# DAC8728_Output-buffers.net
KiCad netlist of a schematic drawn in Altium Designer
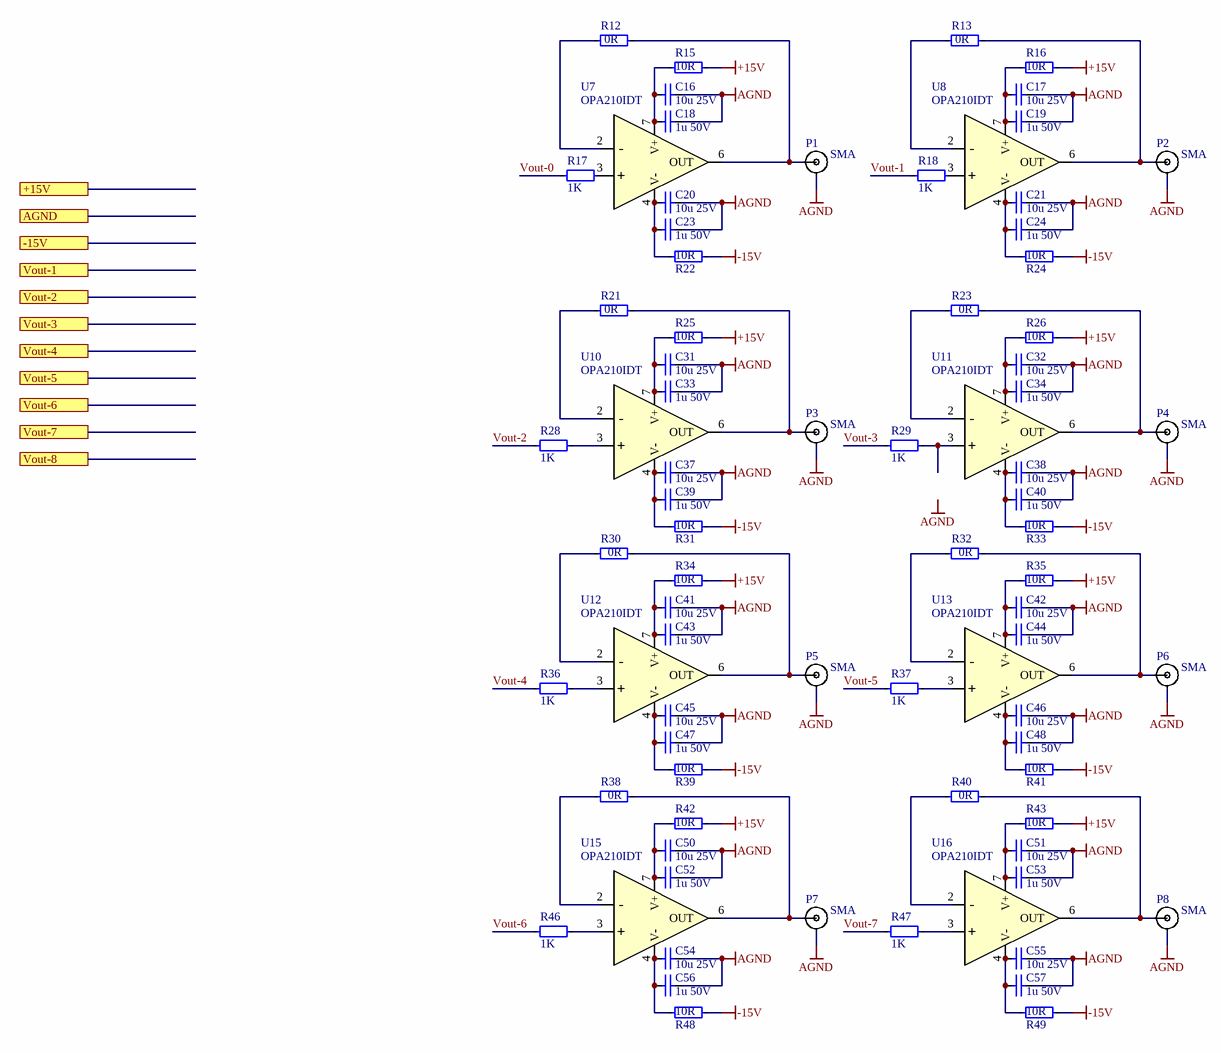
[diagram p0: DAC8728_Output-buffers.SchDoc]

(export (version "E")
  (design (tool "Eeschema 10.0.6"))
  (components
    (comp (ref "C16")
      (value "10u 25V")
      (footprint "cap0805MD")
      (fields
        (field (name "VOLTAGE") "25V")
        (field (name "AUTHOR") "EB")
        (field (name "CHECKED BY") "Unchecked")
      )
      (libsource (lib "TC_Parts") (part "capacitor"))
    )
    (comp (ref "C17")
      (value "10u 25V")
      (footprint "cap0805MD")
      (fields
        (field (name "VOLTAGE") "25V")
        (field (name "AUTHOR") "EB")
        (field (name "CHECKED BY") "Unchecked")
      )
      (libsource (lib "TC_Parts") (part "capacitor"))
    )
    (comp (ref "C18")
      (value "1u 50V")
      (footprint "cap0603MD")
      (fields
        (field (name "VOLTAGE") "50V")
        (field (name "AUTHOR") "Twe")
        (field (name "CHECKED BY") "Unchecked")
      )
      (libsource (lib "TC_Parts") (part "capacitor"))
    )
    (comp (ref "C19")
      (value "1u 50V")
      (footprint "cap0603MD")
      (fields
        (field (name "VOLTAGE") "50V")
        (field (name "AUTHOR") "Twe")
        (field (name "CHECKED BY") "Unchecked")
      )
      (libsource (lib "TC_Parts") (part "capacitor"))
    )
    (comp (ref "C20")
      (value "10u 25V")
      (footprint "cap0805MD")
      (fields
        (field (name "VOLTAGE") "25V")
        (field (name "AUTHOR") "EB")
        (field (name "CHECKED BY") "Unchecked")
      )
      (libsource (lib "TC_Parts") (part "capacitor"))
    )
    (comp (ref "C21")
      (value "10u 25V")
      (footprint "cap0805MD")
      (fields
        (field (name "VOLTAGE") "25V")
        (field (name "AUTHOR") "EB")
        (field (name "CHECKED BY") "Unchecked")
      )
      (libsource (lib "TC_Parts") (part "capacitor"))
    )
    (comp (ref "C23")
      (value "1u 50V")
      (footprint "cap0603MD")
      (fields
        (field (name "VOLTAGE") "50V")
        (field (name "AUTHOR") "Twe")
        (field (name "CHECKED BY") "Unchecked")
      )
      (libsource (lib "TC_Parts") (part "capacitor"))
    )
    (comp (ref "C24")
      (value "1u 50V")
      (footprint "cap0603MD")
      (fields
        (field (name "VOLTAGE") "50V")
        (field (name "AUTHOR") "Twe")
        (field (name "CHECKED BY") "Unchecked")
      )
      (libsource (lib "TC_Parts") (part "capacitor"))
    )
    (comp (ref "C31")
      (value "10u 25V")
      (footprint "cap0805MD")
      (fields
        (field (name "VOLTAGE") "25V")
        (field (name "AUTHOR") "EB")
        (field (name "CHECKED BY") "Unchecked")
      )
      (libsource (lib "TC_Parts") (part "capacitor"))
    )
    (comp (ref "C32")
      (value "10u 25V")
      (footprint "cap0805MD")
      (fields
        (field (name "VOLTAGE") "25V")
        (field (name "AUTHOR") "EB")
        (field (name "CHECKED BY") "Unchecked")
      )
      (libsource (lib "TC_Parts") (part "capacitor"))
    )
    (comp (ref "C33")
      (value "1u 50V")
      (footprint "cap0603MD")
      (fields
        (field (name "VOLTAGE") "50V")
        (field (name "AUTHOR") "Twe")
        (field (name "CHECKED BY") "Unchecked")
      )
      (libsource (lib "TC_Parts") (part "capacitor"))
    )
    (comp (ref "C34")
      (value "1u 50V")
      (footprint "cap0603MD")
      (fields
        (field (name "VOLTAGE") "50V")
        (field (name "AUTHOR") "Twe")
        (field (name "CHECKED BY") "Unchecked")
      )
      (libsource (lib "TC_Parts") (part "capacitor"))
    )
    (comp (ref "C37")
      (value "10u 25V")
      (footprint "cap0805MD")
      (fields
        (field (name "VOLTAGE") "25V")
        (field (name "AUTHOR") "EB")
        (field (name "CHECKED BY") "Unchecked")
      )
      (libsource (lib "TC_Parts") (part "capacitor"))
    )
    (comp (ref "C38")
      (value "10u 25V")
      (footprint "cap0805MD")
      (fields
        (field (name "VOLTAGE") "25V")
        (field (name "AUTHOR") "EB")
        (field (name "CHECKED BY") "Unchecked")
      )
      (libsource (lib "TC_Parts") (part "capacitor"))
    )
    (comp (ref "C39")
      (value "1u 50V")
      (footprint "cap0603MD")
      (fields
        (field (name "VOLTAGE") "50V")
        (field (name "AUTHOR") "Twe")
        (field (name "CHECKED BY") "Unchecked")
      )
      (libsource (lib "TC_Parts") (part "capacitor"))
    )
    (comp (ref "C40")
      (value "1u 50V")
      (footprint "cap0603MD")
      (fields
        (field (name "VOLTAGE") "50V")
        (field (name "AUTHOR") "Twe")
        (field (name "CHECKED BY") "Unchecked")
      )
      (libsource (lib "TC_Parts") (part "capacitor"))
    )
    (comp (ref "C41")
      (value "10u 25V")
      (footprint "cap0805MD")
      (fields
        (field (name "VOLTAGE") "25V")
        (field (name "AUTHOR") "EB")
        (field (name "CHECKED BY") "Unchecked")
      )
      (libsource (lib "TC_Parts") (part "capacitor"))
    )
    (comp (ref "C42")
      (value "10u 25V")
      (footprint "cap0805MD")
      (fields
        (field (name "VOLTAGE") "25V")
        (field (name "AUTHOR") "EB")
        (field (name "CHECKED BY") "Unchecked")
      )
      (libsource (lib "TC_Parts") (part "capacitor"))
    )
    (comp (ref "C43")
      (value "1u 50V")
      (footprint "cap0603MD")
      (fields
        (field (name "VOLTAGE") "50V")
        (field (name "AUTHOR") "Twe")
        (field (name "CHECKED BY") "Unchecked")
      )
      (libsource (lib "TC_Parts") (part "capacitor"))
    )
    (comp (ref "C44")
      (value "1u 50V")
      (footprint "cap0603MD")
      (fields
        (field (name "VOLTAGE") "50V")
        (field (name "AUTHOR") "Twe")
        (field (name "CHECKED BY") "Unchecked")
      )
      (libsource (lib "TC_Parts") (part "capacitor"))
    )
    (comp (ref "C45")
      (value "10u 25V")
      (footprint "cap0805MD")
      (fields
        (field (name "VOLTAGE") "25V")
        (field (name "AUTHOR") "EB")
        (field (name "CHECKED BY") "Unchecked")
      )
      (libsource (lib "TC_Parts") (part "capacitor"))
    )
    (comp (ref "C46")
      (value "10u 25V")
      (footprint "cap0805MD")
      (fields
        (field (name "VOLTAGE") "25V")
        (field (name "AUTHOR") "EB")
        (field (name "CHECKED BY") "Unchecked")
      )
      (libsource (lib "TC_Parts") (part "capacitor"))
    )
    (comp (ref "C47")
      (value "1u 50V")
      (footprint "cap0603MD")
      (fields
        (field (name "VOLTAGE") "50V")
        (field (name "AUTHOR") "Twe")
        (field (name "CHECKED BY") "Unchecked")
      )
      (libsource (lib "TC_Parts") (part "capacitor"))
    )
    (comp (ref "C48")
      (value "1u 50V")
      (footprint "cap0603MD")
      (fields
        (field (name "VOLTAGE") "50V")
        (field (name "AUTHOR") "Twe")
        (field (name "CHECKED BY") "Unchecked")
      )
      (libsource (lib "TC_Parts") (part "capacitor"))
    )
    (comp (ref "C50")
      (value "10u 25V")
      (footprint "cap0805MD")
      (fields
        (field (name "VOLTAGE") "25V")
        (field (name "AUTHOR") "EB")
        (field (name "CHECKED BY") "Unchecked")
      )
      (libsource (lib "TC_Parts") (part "capacitor"))
    )
    (comp (ref "C51")
      (value "10u 25V")
      (footprint "cap0805MD")
      (fields
        (field (name "VOLTAGE") "25V")
        (field (name "AUTHOR") "EB")
        (field (name "CHECKED BY") "Unchecked")
      )
      (libsource (lib "TC_Parts") (part "capacitor"))
    )
    (comp (ref "C52")
      (value "1u 50V")
      (footprint "cap0603MD")
      (fields
        (field (name "VOLTAGE") "50V")
        (field (name "AUTHOR") "Twe")
        (field (name "CHECKED BY") "Unchecked")
      )
      (libsource (lib "TC_Parts") (part "capacitor"))
    )
    (comp (ref "C53")
      (value "1u 50V")
      (footprint "cap0603MD")
      (fields
        (field (name "VOLTAGE") "50V")
        (field (name "AUTHOR") "Twe")
        (field (name "CHECKED BY") "Unchecked")
      )
      (libsource (lib "TC_Parts") (part "capacitor"))
    )
    (comp (ref "C54")
      (value "10u 25V")
      (footprint "cap0805MD")
      (fields
        (field (name "VOLTAGE") "25V")
        (field (name "AUTHOR") "EB")
        (field (name "CHECKED BY") "Unchecked")
      )
      (libsource (lib "TC_Parts") (part "capacitor"))
    )
    (comp (ref "C55")
      (value "10u 25V")
      (footprint "cap0805MD")
      (fields
        (field (name "VOLTAGE") "25V")
        (field (name "AUTHOR") "EB")
        (field (name "CHECKED BY") "Unchecked")
      )
      (libsource (lib "TC_Parts") (part "capacitor"))
    )
    (comp (ref "C56")
      (value "1u 50V")
      (footprint "cap0603MD")
      (fields
        (field (name "VOLTAGE") "50V")
        (field (name "AUTHOR") "Twe")
        (field (name "CHECKED BY") "Unchecked")
      )
      (libsource (lib "TC_Parts") (part "capacitor"))
    )
    (comp (ref "C57")
      (value "1u 50V")
      (footprint "cap0603MD")
      (fields
        (field (name "VOLTAGE") "50V")
        (field (name "AUTHOR") "Twe")
        (field (name "CHECKED BY") "Unchecked")
      )
      (libsource (lib "TC_Parts") (part "capacitor"))
    )
    (comp (ref "P1")
      (value "SMA")
      (footprint "619540-1")
      (description "SMA right angle through hole, 19mm, 50 Ohm")
      (fields
        (field (name "MANUFACTURER") "TE connectivity")
        (field (name "AUTHOR") "EB")
        (field (name "CHECKED BY") "Unchecked")
      )
      (libsource (lib "TC_Parts") (part "SMA"))
    )
    (comp (ref "P2")
      (value "SMA")
      (footprint "619540-1")
      (description "SMA right angle through hole, 19mm, 50 Ohm")
      (fields
        (field (name "MANUFACTURER") "TE connectivity")
        (field (name "AUTHOR") "EB")
        (field (name "CHECKED BY") "Unchecked")
      )
      (libsource (lib "TC_Parts") (part "SMA"))
    )
    (comp (ref "P3")
      (value "SMA")
      (footprint "619540-1")
      (description "SMA right angle through hole, 19mm, 50 Ohm")
      (fields
        (field (name "MANUFACTURER") "TE connectivity")
        (field (name "AUTHOR") "EB")
        (field (name "CHECKED BY") "Unchecked")
      )
      (libsource (lib "TC_Parts") (part "SMA"))
    )
    (comp (ref "P4")
      (value "SMA")
      (footprint "619540-1")
      (description "SMA right angle through hole, 19mm, 50 Ohm")
      (fields
        (field (name "MANUFACTURER") "TE connectivity")
        (field (name "AUTHOR") "EB")
        (field (name "CHECKED BY") "Unchecked")
      )
      (libsource (lib "TC_Parts") (part "SMA"))
    )
    (comp (ref "P5")
      (value "SMA")
      (footprint "619540-1")
      (description "SMA right angle through hole, 19mm, 50 Ohm")
      (fields
        (field (name "MANUFACTURER") "TE connectivity")
        (field (name "AUTHOR") "EB")
        (field (name "CHECKED BY") "Unchecked")
      )
      (libsource (lib "TC_Parts") (part "SMA"))
    )
    (comp (ref "P6")
      (value "SMA")
      (footprint "619540-1")
      (description "SMA right angle through hole, 19mm, 50 Ohm")
      (fields
        (field (name "MANUFACTURER") "TE connectivity")
        (field (name "AUTHOR") "EB")
        (field (name "CHECKED BY") "Unchecked")
      )
      (libsource (lib "TC_Parts") (part "SMA"))
    )
    (comp (ref "P7")
      (value "SMA")
      (footprint "619540-1")
      (description "SMA right angle through hole, 19mm, 50 Ohm")
      (fields
        (field (name "MANUFACTURER") "TE connectivity")
        (field (name "AUTHOR") "EB")
        (field (name "CHECKED BY") "Unchecked")
      )
      (libsource (lib "TC_Parts") (part "SMA"))
    )
    (comp (ref "P8")
      (value "SMA")
      (footprint "619540-1")
      (description "SMA right angle through hole, 19mm, 50 Ohm")
      (fields
        (field (name "MANUFACTURER") "TE connectivity")
        (field (name "AUTHOR") "EB")
        (field (name "CHECKED BY") "Unchecked")
      )
      (libsource (lib "TC_Parts") (part "SMA"))
    )
    (comp (ref "R12")
      (value "0R")
      (footprint "res0603MD")
      (fields (field (name "AUTHOR") "Twe") (field (name "CHECKED BY") "Unchecked"))
      (libsource (lib "") (part "resistor_1"))
    )
    (comp (ref "R13")
      (value "0R")
      (footprint "res0603MD")
      (fields (field (name "AUTHOR") "Twe") (field (name "CHECKED BY") "Unchecked"))
      (libsource (lib "") (part "resistor_1"))
    )
    (comp (ref "R15")
      (value "10R")
      (footprint "res0603MD")
      (fields (field (name "AUTHOR") "Twe") (field (name "CHECKED BY") "Unchecked"))
      (libsource (lib "TC_Parts") (part "resistor"))
    )
    (comp (ref "R16")
      (value "10R")
      (footprint "res0603MD")
      (fields (field (name "AUTHOR") "Twe") (field (name "CHECKED BY") "Unchecked"))
      (libsource (lib "TC_Parts") (part "resistor"))
    )
    (comp (ref "R17")
      (value "1K")
      (footprint "res0603MD")
      (fields (field (name "AUTHOR") "Twe") (field (name "CHECKED BY") "Unchecked"))
      (libsource (lib "") (part "resistor_1"))
    )
    (comp (ref "R18")
      (value "1K")
      (footprint "res0603MD")
      (fields (field (name "AUTHOR") "Twe") (field (name "CHECKED BY") "Unchecked"))
      (libsource (lib "") (part "resistor_1"))
    )
    (comp (ref "R21")
      (value "0R")
      (footprint "res0603MD")
      (fields (field (name "AUTHOR") "Twe") (field (name "CHECKED BY") "Unchecked"))
      (libsource (lib "") (part "resistor_1"))
    )
    (comp (ref "R22")
      (value "10R")
      (footprint "res0603MD")
      (fields (field (name "AUTHOR") "Twe") (field (name "CHECKED BY") "Unchecked"))
      (libsource (lib "TC_Parts") (part "resistor"))
    )
    (comp (ref "R23")
      (value "0R")
      (footprint "res0603MD")
      (fields (field (name "AUTHOR") "Twe") (field (name "CHECKED BY") "Unchecked"))
      (libsource (lib "") (part "resistor_1"))
    )
    (comp (ref "R24")
      (value "10R")
      (footprint "res0603MD")
      (fields (field (name "AUTHOR") "Twe") (field (name "CHECKED BY") "Unchecked"))
      (libsource (lib "TC_Parts") (part "resistor"))
    )
    (comp (ref "R25")
      (value "10R")
      (footprint "res0603MD")
      (fields (field (name "AUTHOR") "Twe") (field (name "CHECKED BY") "Unchecked"))
      (libsource (lib "TC_Parts") (part "resistor"))
    )
    (comp (ref "R26")
      (value "10R")
      (footprint "res0603MD")
      (fields (field (name "AUTHOR") "Twe") (field (name "CHECKED BY") "Unchecked"))
      (libsource (lib "TC_Parts") (part "resistor"))
    )
    (comp (ref "R28")
      (value "1K")
      (footprint "res0603MD")
      (fields (field (name "AUTHOR") "Twe") (field (name "CHECKED BY") "Unchecked"))
      (libsource (lib "") (part "resistor_1"))
    )
    (comp (ref "R29")
      (value "1K")
      (footprint "res0603MD")
      (fields (field (name "AUTHOR") "Twe") (field (name "CHECKED BY") "Unchecked"))
      (libsource (lib "") (part "resistor_1"))
    )
    (comp (ref "R30")
      (value "0R")
      (footprint "res0603MD")
      (fields (field (name "AUTHOR") "Twe") (field (name "CHECKED BY") "Unchecked"))
      (libsource (lib "") (part "resistor_1"))
    )
    (comp (ref "R31")
      (value "10R")
      (footprint "res0603MD")
      (fields (field (name "AUTHOR") "Twe") (field (name "CHECKED BY") "Unchecked"))
      (libsource (lib "TC_Parts") (part "resistor"))
    )
    (comp (ref "R32")
      (value "0R")
      (footprint "res0603MD")
      (fields (field (name "AUTHOR") "Twe") (field (name "CHECKED BY") "Unchecked"))
      (libsource (lib "") (part "resistor_1"))
    )
    (comp (ref "R33")
      (value "10R")
      (footprint "res0603MD")
      (fields (field (name "AUTHOR") "Twe") (field (name "CHECKED BY") "Unchecked"))
      (libsource (lib "TC_Parts") (part "resistor"))
    )
    (comp (ref "R34")
      (value "10R")
      (footprint "res0603MD")
      (fields (field (name "AUTHOR") "Twe") (field (name "CHECKED BY") "Unchecked"))
      (libsource (lib "TC_Parts") (part "resistor"))
    )
    (comp (ref "R35")
      (value "10R")
      (footprint "res0603MD")
      (fields (field (name "AUTHOR") "Twe") (field (name "CHECKED BY") "Unchecked"))
      (libsource (lib "TC_Parts") (part "resistor"))
    )
    (comp (ref "R36")
      (value "1K")
      (footprint "res0603MD")
      (fields (field (name "AUTHOR") "Twe") (field (name "CHECKED BY") "Unchecked"))
      (libsource (lib "") (part "resistor_1"))
    )
    (comp (ref "R37")
      (value "1K")
      (footprint "res0603MD")
      (fields (field (name "AUTHOR") "Twe") (field (name "CHECKED BY") "Unchecked"))
      (libsource (lib "") (part "resistor_1"))
    )
    (comp (ref "R38")
      (value "0R")
      (footprint "res0603MD")
      (fields (field (name "AUTHOR") "Twe") (field (name "CHECKED BY") "Unchecked"))
      (libsource (lib "") (part "resistor_1"))
    )
    (comp (ref "R39")
      (value "10R")
      (footprint "res0603MD")
      (fields (field (name "AUTHOR") "Twe") (field (name "CHECKED BY") "Unchecked"))
      (libsource (lib "TC_Parts") (part "resistor"))
    )
    (comp (ref "R40")
      (value "0R")
      (footprint "res0603MD")
      (fields (field (name "AUTHOR") "Twe") (field (name "CHECKED BY") "Unchecked"))
      (libsource (lib "") (part "resistor_1"))
    )
    (comp (ref "R41")
      (value "10R")
      (footprint "res0603MD")
      (fields (field (name "AUTHOR") "Twe") (field (name "CHECKED BY") "Unchecked"))
      (libsource (lib "TC_Parts") (part "resistor"))
    )
    (comp (ref "R42")
      (value "10R")
      (footprint "res0603MD")
      (fields (field (name "AUTHOR") "Twe") (field (name "CHECKED BY") "Unchecked"))
      (libsource (lib "TC_Parts") (part "resistor"))
    )
    (comp (ref "R43")
      (value "10R")
      (footprint "res0603MD")
      (fields (field (name "AUTHOR") "Twe") (field (name "CHECKED BY") "Unchecked"))
      (libsource (lib "TC_Parts") (part "resistor"))
    )
    (comp (ref "R46")
      (value "1K")
      (footprint "res0603MD")
      (fields (field (name "AUTHOR") "Twe") (field (name "CHECKED BY") "Unchecked"))
      (libsource (lib "") (part "resistor_1"))
    )
    (comp (ref "R47")
      (value "1K")
      (footprint "res0603MD")
      (fields (field (name "AUTHOR") "Twe") (field (name "CHECKED BY") "Unchecked"))
      (libsource (lib "") (part "resistor_1"))
    )
    (comp (ref "R48")
      (value "10R")
      (footprint "res0603MD")
      (fields (field (name "AUTHOR") "Twe") (field (name "CHECKED BY") "Unchecked"))
      (libsource (lib "TC_Parts") (part "resistor"))
    )
    (comp (ref "R49")
      (value "10R")
      (footprint "res0603MD")
      (fields (field (name "AUTHOR") "Twe") (field (name "CHECKED BY") "Unchecked"))
      (libsource (lib "TC_Parts") (part "resistor"))
    )
    (comp (ref "U7")
      (value "OPA210IDT")
      (footprint "SOIC127P600X175-8N")
      (description "UltraLow Noise-drift, high precision, Low-Power, 36-V")
      (fields
        (field (name "MANUFACTURER") "Analog Devices")
        (field (name "AUTHOR") "EB")
        (field (name "CHECKED BY") "Unchecked")
      )
      (libsource (lib "TC_Parts") (part "OPA210IDT"))
    )
    (comp (ref "U8")
      (value "OPA210IDT")
      (footprint "SOIC127P600X175-8N")
      (description "UltraLow Noise-drift, high precision, Low-Power, 36-V")
      (fields
        (field (name "MANUFACTURER") "Analog Devices")
        (field (name "AUTHOR") "EB")
        (field (name "CHECKED BY") "Unchecked")
      )
      (libsource (lib "TC_Parts") (part "OPA210IDT"))
    )
    (comp (ref "U10")
      (value "OPA210IDT")
      (footprint "SOIC127P600X175-8N")
      (description "UltraLow Noise-drift, high precision, Low-Power, 36-V")
      (fields
        (field (name "MANUFACTURER") "Analog Devices")
        (field (name "AUTHOR") "EB")
        (field (name "CHECKED BY") "Unchecked")
      )
      (libsource (lib "TC_Parts") (part "OPA210IDT"))
    )
    (comp (ref "U11")
      (value "OPA210IDT")
      (footprint "SOIC127P600X175-8N")
      (description "UltraLow Noise-drift, high precision, Low-Power, 36-V")
      (fields
        (field (name "MANUFACTURER") "Analog Devices")
        (field (name "AUTHOR") "EB")
        (field (name "CHECKED BY") "Unchecked")
      )
      (libsource (lib "TC_Parts") (part "OPA210IDT"))
    )
    (comp (ref "U12")
      (value "OPA210IDT")
      (footprint "SOIC127P600X175-8N")
      (description "UltraLow Noise-drift, high precision, Low-Power, 36-V")
      (fields
        (field (name "MANUFACTURER") "Analog Devices")
        (field (name "AUTHOR") "EB")
        (field (name "CHECKED BY") "Unchecked")
      )
      (libsource (lib "TC_Parts") (part "OPA210IDT"))
    )
    (comp (ref "U13")
      (value "OPA210IDT")
      (footprint "SOIC127P600X175-8N")
      (description "UltraLow Noise-drift, high precision, Low-Power, 36-V")
      (fields
        (field (name "MANUFACTURER") "Analog Devices")
        (field (name "AUTHOR") "EB")
        (field (name "CHECKED BY") "Unchecked")
      )
      (libsource (lib "TC_Parts") (part "OPA210IDT"))
    )
    (comp (ref "U15")
      (value "OPA210IDT")
      (footprint "SOIC127P600X175-8N")
      (description "UltraLow Noise-drift, high precision, Low-Power, 36-V")
      (fields
        (field (name "MANUFACTURER") "Analog Devices")
        (field (name "AUTHOR") "EB")
        (field (name "CHECKED BY") "Unchecked")
      )
      (libsource (lib "TC_Parts") (part "OPA210IDT"))
    )
    (comp (ref "U16")
      (value "OPA210IDT")
      (footprint "SOIC127P600X175-8N")
      (description "UltraLow Noise-drift, high precision, Low-Power, 36-V")
      (fields
        (field (name "MANUFACTURER") "Analog Devices")
        (field (name "AUTHOR") "EB")
        (field (name "CHECKED BY") "Unchecked")
      )
      (libsource (lib "TC_Parts") (part "OPA210IDT"))
    )
  )
  (nets
    (net (code "1") (name "+15V") (class "Default")
      (node (ref "R15") (pin "1") (pinfunction "1_1") (pintype "passive"))
      (node (ref "R16") (pin "1") (pinfunction "1_1") (pintype "passive"))
      (node (ref "R25") (pin "1") (pinfunction "1_1") (pintype "passive"))
      (node (ref "R26") (pin "1") (pinfunction "1_1") (pintype "passive"))
      (node (ref "R34") (pin "1") (pinfunction "1_1") (pintype "passive"))
      (node (ref "R35") (pin "1") (pinfunction "1_1") (pintype "passive"))
      (node (ref "R42") (pin "1") (pinfunction "1_1") (pintype "passive"))
      (node (ref "R43") (pin "1") (pinfunction "1_1") (pintype "passive"))
    )
    (net (code "2") (name "-15V") (class "Default")
      (node (ref "R22") (pin "1") (pinfunction "1_1") (pintype "passive"))
      (node (ref "R24") (pin "1") (pinfunction "1_1") (pintype "passive"))
      (node (ref "R31") (pin "1") (pinfunction "1_1") (pintype "passive"))
      (node (ref "R33") (pin "1") (pinfunction "1_1") (pintype "passive"))
      (node (ref "R39") (pin "1") (pinfunction "1_1") (pintype "passive"))
      (node (ref "R41") (pin "1") (pinfunction "1_1") (pintype "passive"))
      (node (ref "R48") (pin "1") (pinfunction "1_1") (pintype "passive"))
      (node (ref "R49") (pin "1") (pinfunction "1_1") (pintype "passive"))
    )
    (net (code "3") (name "/Vout-0") (class "Default")
      (node (ref "R17") (pin "1") (pinfunction "1_1") (pintype "passive"))
    )
    (net (code "4") (name "/Vout-1") (class "Default")
      (node (ref "R18") (pin "1") (pinfunction "1_1") (pintype "passive"))
    )
    (net (code "5") (name "/Vout-2") (class "Default")
      (node (ref "R28") (pin "1") (pinfunction "1_1") (pintype "passive"))
    )
    (net (code "6") (name "/Vout-3") (class "Default")
      (node (ref "R29") (pin "1") (pinfunction "1_1") (pintype "passive"))
    )
    (net (code "7") (name "/Vout-4") (class "Default")
      (node (ref "R36") (pin "1") (pinfunction "1_1") (pintype "passive"))
    )
    (net (code "8") (name "/Vout-5") (class "Default")
      (node (ref "R37") (pin "1") (pinfunction "1_1") (pintype "passive"))
    )
    (net (code "9") (name "/Vout-6") (class "Default")
      (node (ref "R46") (pin "1") (pinfunction "1_1") (pintype "passive"))
    )
    (net (code "10") (name "/Vout-7") (class "Default")
      (node (ref "R47") (pin "1") (pinfunction "1_1") (pintype "passive"))
    )
    (net (code "12") (name "AGND") (class "Default")
      (node (ref "C16") (pin "2") (pinfunction "2_2") (pintype "passive"))
      (node (ref "C17") (pin "2") (pinfunction "2_2") (pintype "passive"))
      (node (ref "C18") (pin "2") (pinfunction "2_2") (pintype "passive"))
      (node (ref "C19") (pin "2") (pinfunction "2_2") (pintype "passive"))
      (node (ref "C20") (pin "2") (pinfunction "2_2") (pintype "passive"))
      (node (ref "C21") (pin "2") (pinfunction "2_2") (pintype "passive"))
      (node (ref "C23") (pin "2") (pinfunction "2_2") (pintype "passive"))
      (node (ref "C24") (pin "2") (pinfunction "2_2") (pintype "passive"))
      (node (ref "C31") (pin "2") (pinfunction "2_2") (pintype "passive"))
      (node (ref "C32") (pin "2") (pinfunction "2_2") (pintype "passive"))
      (node (ref "C33") (pin "2") (pinfunction "2_2") (pintype "passive"))
      (node (ref "C34") (pin "2") (pinfunction "2_2") (pintype "passive"))
      (node (ref "C37") (pin "2") (pinfunction "2_2") (pintype "passive"))
      (node (ref "C38") (pin "2") (pinfunction "2_2") (pintype "passive"))
      (node (ref "C39") (pin "2") (pinfunction "2_2") (pintype "passive"))
      (node (ref "C40") (pin "2") (pinfunction "2_2") (pintype "passive"))
      (node (ref "C41") (pin "2") (pinfunction "2_2") (pintype "passive"))
      (node (ref "C42") (pin "2") (pinfunction "2_2") (pintype "passive"))
      (node (ref "C43") (pin "2") (pinfunction "2_2") (pintype "passive"))
      (node (ref "C44") (pin "2") (pinfunction "2_2") (pintype "passive"))
      (node (ref "C45") (pin "2") (pinfunction "2_2") (pintype "passive"))
      (node (ref "C46") (pin "2") (pinfunction "2_2") (pintype "passive"))
      (node (ref "C47") (pin "2") (pinfunction "2_2") (pintype "passive"))
      (node (ref "C48") (pin "2") (pinfunction "2_2") (pintype "passive"))
      (node (ref "C50") (pin "2") (pinfunction "2_2") (pintype "passive"))
      (node (ref "C51") (pin "2") (pinfunction "2_2") (pintype "passive"))
      (node (ref "C52") (pin "2") (pinfunction "2_2") (pintype "passive"))
      (node (ref "C53") (pin "2") (pinfunction "2_2") (pintype "passive"))
      (node (ref "C54") (pin "2") (pinfunction "2_2") (pintype "passive"))
      (node (ref "C55") (pin "2") (pinfunction "2_2") (pintype "passive"))
      (node (ref "C56") (pin "2") (pinfunction "2_2") (pintype "passive"))
      (node (ref "C57") (pin "2") (pinfunction "2_2") (pintype "passive"))
      (node (ref "P1") (pin "2") (pinfunction "2_2") (pintype "passive"))
      (node (ref "P2") (pin "2") (pinfunction "2_2") (pintype "passive"))
      (node (ref "P3") (pin "2") (pinfunction "2_2") (pintype "passive"))
      (node (ref "P4") (pin "2") (pinfunction "2_2") (pintype "passive"))
      (node (ref "P5") (pin "2") (pinfunction "2_2") (pintype "passive"))
      (node (ref "P6") (pin "2") (pinfunction "2_2") (pintype "passive"))
      (node (ref "P7") (pin "2") (pinfunction "2_2") (pintype "passive"))
      (node (ref "P8") (pin "2") (pinfunction "2_2") (pintype "passive"))
    )
    (net (code "13") (name "Net-(U7-+)") (class "Default")
      (node (ref "R17") (pin "2") (pinfunction "2_2") (pintype "passive"))
      (node (ref "U7") (pin "3") (pinfunction "+_3") (pintype "passive"))
    )
    (net (code "14") (name "Net-(U7--)") (class "Default")
      (node (ref "R12") (pin "1") (pinfunction "1_1") (pintype "passive"))
      (node (ref "U7") (pin "2") (pinfunction "-_2") (pintype "passive"))
    )
    (net (code "15") (name "Net-(U7-OUT)") (class "Default")
      (node (ref "P1") (pin "1") (pinfunction "1_1") (pintype "passive"))
      (node (ref "R12") (pin "2") (pinfunction "2_2") (pintype "passive"))
      (node (ref "U7") (pin "6") (pinfunction "OUT_6") (pintype "passive"))
    )
    (net (code "16") (name "Net-(U7-V+)") (class "Default")
      (node (ref "C16") (pin "1") (pinfunction "1_1") (pintype "passive"))
      (node (ref "C18") (pin "1") (pinfunction "1_1") (pintype "passive"))
      (node (ref "R15") (pin "2") (pinfunction "2_2") (pintype "passive"))
      (node (ref "U7") (pin "7") (pinfunction "V+_7") (pintype "passive"))
    )
    (net (code "17") (name "Net-(U7-V-)") (class "Default")
      (node (ref "C20") (pin "1") (pinfunction "1_1") (pintype "passive"))
      (node (ref "C23") (pin "1") (pinfunction "1_1") (pintype "passive"))
      (node (ref "R22") (pin "2") (pinfunction "2_2") (pintype "passive"))
      (node (ref "U7") (pin "4") (pinfunction "V-_4") (pintype "passive"))
    )
    (net (code "18") (name "Net-(U8-+)") (class "Default")
      (node (ref "R18") (pin "2") (pinfunction "2_2") (pintype "passive"))
      (node (ref "U8") (pin "3") (pinfunction "+_3") (pintype "passive"))
    )
    (net (code "19") (name "Net-(U8--)") (class "Default")
      (node (ref "R13") (pin "1") (pinfunction "1_1") (pintype "passive"))
      (node (ref "U8") (pin "2") (pinfunction "-_2") (pintype "passive"))
    )
    (net (code "20") (name "Net-(U8-OUT)") (class "Default")
      (node (ref "P2") (pin "1") (pinfunction "1_1") (pintype "passive"))
      (node (ref "R13") (pin "2") (pinfunction "2_2") (pintype "passive"))
      (node (ref "U8") (pin "6") (pinfunction "OUT_6") (pintype "passive"))
    )
    (net (code "21") (name "Net-(U8-V+)") (class "Default")
      (node (ref "C17") (pin "1") (pinfunction "1_1") (pintype "passive"))
      (node (ref "C19") (pin "1") (pinfunction "1_1") (pintype "passive"))
      (node (ref "R16") (pin "2") (pinfunction "2_2") (pintype "passive"))
      (node (ref "U8") (pin "7") (pinfunction "V+_7") (pintype "passive"))
    )
    (net (code "22") (name "Net-(U8-V-)") (class "Default")
      (node (ref "C21") (pin "1") (pinfunction "1_1") (pintype "passive"))
      (node (ref "C24") (pin "1") (pinfunction "1_1") (pintype "passive"))
      (node (ref "R24") (pin "2") (pinfunction "2_2") (pintype "passive"))
      (node (ref "U8") (pin "4") (pinfunction "V-_4") (pintype "passive"))
    )
    (net (code "23") (name "Net-(U10-+)") (class "Default")
      (node (ref "R28") (pin "2") (pinfunction "2_2") (pintype "passive"))
      (node (ref "U10") (pin "3") (pinfunction "+_3") (pintype "passive"))
    )
    (net (code "24") (name "Net-(U10--)") (class "Default")
      (node (ref "R21") (pin "1") (pinfunction "1_1") (pintype "passive"))
      (node (ref "U10") (pin "2") (pinfunction "-_2") (pintype "passive"))
    )
    (net (code "25") (name "Net-(U10-OUT)") (class "Default")
      (node (ref "P3") (pin "1") (pinfunction "1_1") (pintype "passive"))
      (node (ref "R21") (pin "2") (pinfunction "2_2") (pintype "passive"))
      (node (ref "U10") (pin "6") (pinfunction "OUT_6") (pintype "passive"))
    )
    (net (code "26") (name "Net-(U10-V+)") (class "Default")
      (node (ref "C31") (pin "1") (pinfunction "1_1") (pintype "passive"))
      (node (ref "C33") (pin "1") (pinfunction "1_1") (pintype "passive"))
      (node (ref "R25") (pin "2") (pinfunction "2_2") (pintype "passive"))
      (node (ref "U10") (pin "7") (pinfunction "V+_7") (pintype "passive"))
    )
    (net (code "27") (name "Net-(U10-V-)") (class "Default")
      (node (ref "C37") (pin "1") (pinfunction "1_1") (pintype "passive"))
      (node (ref "C39") (pin "1") (pinfunction "1_1") (pintype "passive"))
      (node (ref "R31") (pin "2") (pinfunction "2_2") (pintype "passive"))
      (node (ref "U10") (pin "4") (pinfunction "V-_4") (pintype "passive"))
    )
    (net (code "28") (name "Net-(U11-+)") (class "Default")
      (node (ref "R29") (pin "2") (pinfunction "2_2") (pintype "passive"))
      (node (ref "U11") (pin "3") (pinfunction "+_3") (pintype "passive"))
    )
    (net (code "29") (name "Net-(U11--)") (class "Default")
      (node (ref "R23") (pin "1") (pinfunction "1_1") (pintype "passive"))
      (node (ref "U11") (pin "2") (pinfunction "-_2") (pintype "passive"))
    )
    (net (code "30") (name "Net-(U11-OUT)") (class "Default")
      (node (ref "P4") (pin "1") (pinfunction "1_1") (pintype "passive"))
      (node (ref "R23") (pin "2") (pinfunction "2_2") (pintype "passive"))
      (node (ref "U11") (pin "6") (pinfunction "OUT_6") (pintype "passive"))
    )
    (net (code "31") (name "Net-(U11-V+)") (class "Default")
      (node (ref "C32") (pin "1") (pinfunction "1_1") (pintype "passive"))
      (node (ref "C34") (pin "1") (pinfunction "1_1") (pintype "passive"))
      (node (ref "R26") (pin "2") (pinfunction "2_2") (pintype "passive"))
      (node (ref "U11") (pin "7") (pinfunction "V+_7") (pintype "passive"))
    )
    (net (code "32") (name "Net-(U11-V-)") (class "Default")
      (node (ref "C38") (pin "1") (pinfunction "1_1") (pintype "passive"))
      (node (ref "C40") (pin "1") (pinfunction "1_1") (pintype "passive"))
      (node (ref "R33") (pin "2") (pinfunction "2_2") (pintype "passive"))
      (node (ref "U11") (pin "4") (pinfunction "V-_4") (pintype "passive"))
    )
    (net (code "33") (name "Net-(U12-+)") (class "Default")
      (node (ref "R36") (pin "2") (pinfunction "2_2") (pintype "passive"))
      (node (ref "U12") (pin "3") (pinfunction "+_3") (pintype "passive"))
    )
    (net (code "34") (name "Net-(U12--)") (class "Default")
      (node (ref "R30") (pin "1") (pinfunction "1_1") (pintype "passive"))
      (node (ref "U12") (pin "2") (pinfunction "-_2") (pintype "passive"))
    )
    (net (code "35") (name "Net-(U12-OUT)") (class "Default")
      (node (ref "P5") (pin "1") (pinfunction "1_1") (pintype "passive"))
      (node (ref "R30") (pin "2") (pinfunction "2_2") (pintype "passive"))
      (node (ref "U12") (pin "6") (pinfunction "OUT_6") (pintype "passive"))
    )
    (net (code "36") (name "Net-(U12-V+)") (class "Default")
      (node (ref "C41") (pin "1") (pinfunction "1_1") (pintype "passive"))
      (node (ref "C43") (pin "1") (pinfunction "1_1") (pintype "passive"))
      (node (ref "R34") (pin "2") (pinfunction "2_2") (pintype "passive"))
      (node (ref "U12") (pin "7") (pinfunction "V+_7") (pintype "passive"))
    )
    (net (code "37") (name "Net-(U12-V-)") (class "Default")
      (node (ref "C45") (pin "1") (pinfunction "1_1") (pintype "passive"))
      (node (ref "C47") (pin "1") (pinfunction "1_1") (pintype "passive"))
      (node (ref "R39") (pin "2") (pinfunction "2_2") (pintype "passive"))
      (node (ref "U12") (pin "4") (pinfunction "V-_4") (pintype "passive"))
    )
    (net (code "38") (name "Net-(U13-+)") (class "Default")
      (node (ref "R37") (pin "2") (pinfunction "2_2") (pintype "passive"))
      (node (ref "U13") (pin "3") (pinfunction "+_3") (pintype "passive"))
    )
    (net (code "39") (name "Net-(U13--)") (class "Default")
      (node (ref "R32") (pin "1") (pinfunction "1_1") (pintype "passive"))
      (node (ref "U13") (pin "2") (pinfunction "-_2") (pintype "passive"))
    )
    (net (code "40") (name "Net-(U13-OUT)") (class "Default")
      (node (ref "P6") (pin "1") (pinfunction "1_1") (pintype "passive"))
      (node (ref "R32") (pin "2") (pinfunction "2_2") (pintype "passive"))
      (node (ref "U13") (pin "6") (pinfunction "OUT_6") (pintype "passive"))
    )
    (net (code "41") (name "Net-(U13-V+)") (class "Default")
      (node (ref "C42") (pin "1") (pinfunction "1_1") (pintype "passive"))
      (node (ref "C44") (pin "1") (pinfunction "1_1") (pintype "passive"))
      (node (ref "R35") (pin "2") (pinfunction "2_2") (pintype "passive"))
      (node (ref "U13") (pin "7") (pinfunction "V+_7") (pintype "passive"))
    )
    (net (code "42") (name "Net-(U13-V-)") (class "Default")
      (node (ref "C46") (pin "1") (pinfunction "1_1") (pintype "passive"))
      (node (ref "C48") (pin "1") (pinfunction "1_1") (pintype "passive"))
      (node (ref "R41") (pin "2") (pinfunction "2_2") (pintype "passive"))
      (node (ref "U13") (pin "4") (pinfunction "V-_4") (pintype "passive"))
    )
    (net (code "43") (name "Net-(U15-+)") (class "Default")
      (node (ref "R46") (pin "2") (pinfunction "2_2") (pintype "passive"))
      (node (ref "U15") (pin "3") (pinfunction "+_3") (pintype "passive"))
    )
    (net (code "44") (name "Net-(U15--)") (class "Default")
      (node (ref "R38") (pin "1") (pinfunction "1_1") (pintype "passive"))
      (node (ref "U15") (pin "2") (pinfunction "-_2") (pintype "passive"))
    )
    (net (code "45") (name "Net-(U15-OUT)") (class "Default")
      (node (ref "P7") (pin "1") (pinfunction "1_1") (pintype "passive"))
      (node (ref "R38") (pin "2") (pinfunction "2_2") (pintype "passive"))
      (node (ref "U15") (pin "6") (pinfunction "OUT_6") (pintype "passive"))
    )
    (net (code "46") (name "Net-(U15-V+)") (class "Default")
      (node (ref "C50") (pin "1") (pinfunction "1_1") (pintype "passive"))
      (node (ref "C52") (pin "1") (pinfunction "1_1") (pintype "passive"))
      (node (ref "R42") (pin "2") (pinfunction "2_2") (pintype "passive"))
      (node (ref "U15") (pin "7") (pinfunction "V+_7") (pintype "passive"))
    )
    (net (code "47") (name "Net-(U15-V-)") (class "Default")
      (node (ref "C54") (pin "1") (pinfunction "1_1") (pintype "passive"))
      (node (ref "C56") (pin "1") (pinfunction "1_1") (pintype "passive"))
      (node (ref "R48") (pin "2") (pinfunction "2_2") (pintype "passive"))
      (node (ref "U15") (pin "4") (pinfunction "V-_4") (pintype "passive"))
    )
    (net (code "48") (name "Net-(U16-+)") (class "Default")
      (node (ref "R47") (pin "2") (pinfunction "2_2") (pintype "passive"))
      (node (ref "U16") (pin "3") (pinfunction "+_3") (pintype "passive"))
    )
    (net (code "49") (name "Net-(U16--)") (class "Default")
      (node (ref "R40") (pin "1") (pinfunction "1_1") (pintype "passive"))
      (node (ref "U16") (pin "2") (pinfunction "-_2") (pintype "passive"))
    )
    (net (code "50") (name "Net-(U16-OUT)") (class "Default")
      (node (ref "P8") (pin "1") (pinfunction "1_1") (pintype "passive"))
      (node (ref "R40") (pin "2") (pinfunction "2_2") (pintype "passive"))
      (node (ref "U16") (pin "6") (pinfunction "OUT_6") (pintype "passive"))
    )
    (net (code "51") (name "Net-(U16-V+)") (class "Default")
      (node (ref "C51") (pin "1") (pinfunction "1_1") (pintype "passive"))
      (node (ref "C53") (pin "1") (pinfunction "1_1") (pintype "passive"))
      (node (ref "R43") (pin "2") (pinfunction "2_2") (pintype "passive"))
      (node (ref "U16") (pin "7") (pinfunction "V+_7") (pintype "passive"))
    )
    (net (code "52") (name "Net-(U16-V-)") (class "Default")
      (node (ref "C55") (pin "1") (pinfunction "1_1") (pintype "passive"))
      (node (ref "C57") (pin "1") (pinfunction "1_1") (pintype "passive"))
      (node (ref "R49") (pin "2") (pinfunction "2_2") (pintype "passive"))
      (node (ref "U16") (pin "4") (pinfunction "V-_4") (pintype "passive"))
    )
  )
)
